# main.net
KiCad netlist of a schematic drawn in EAGLE
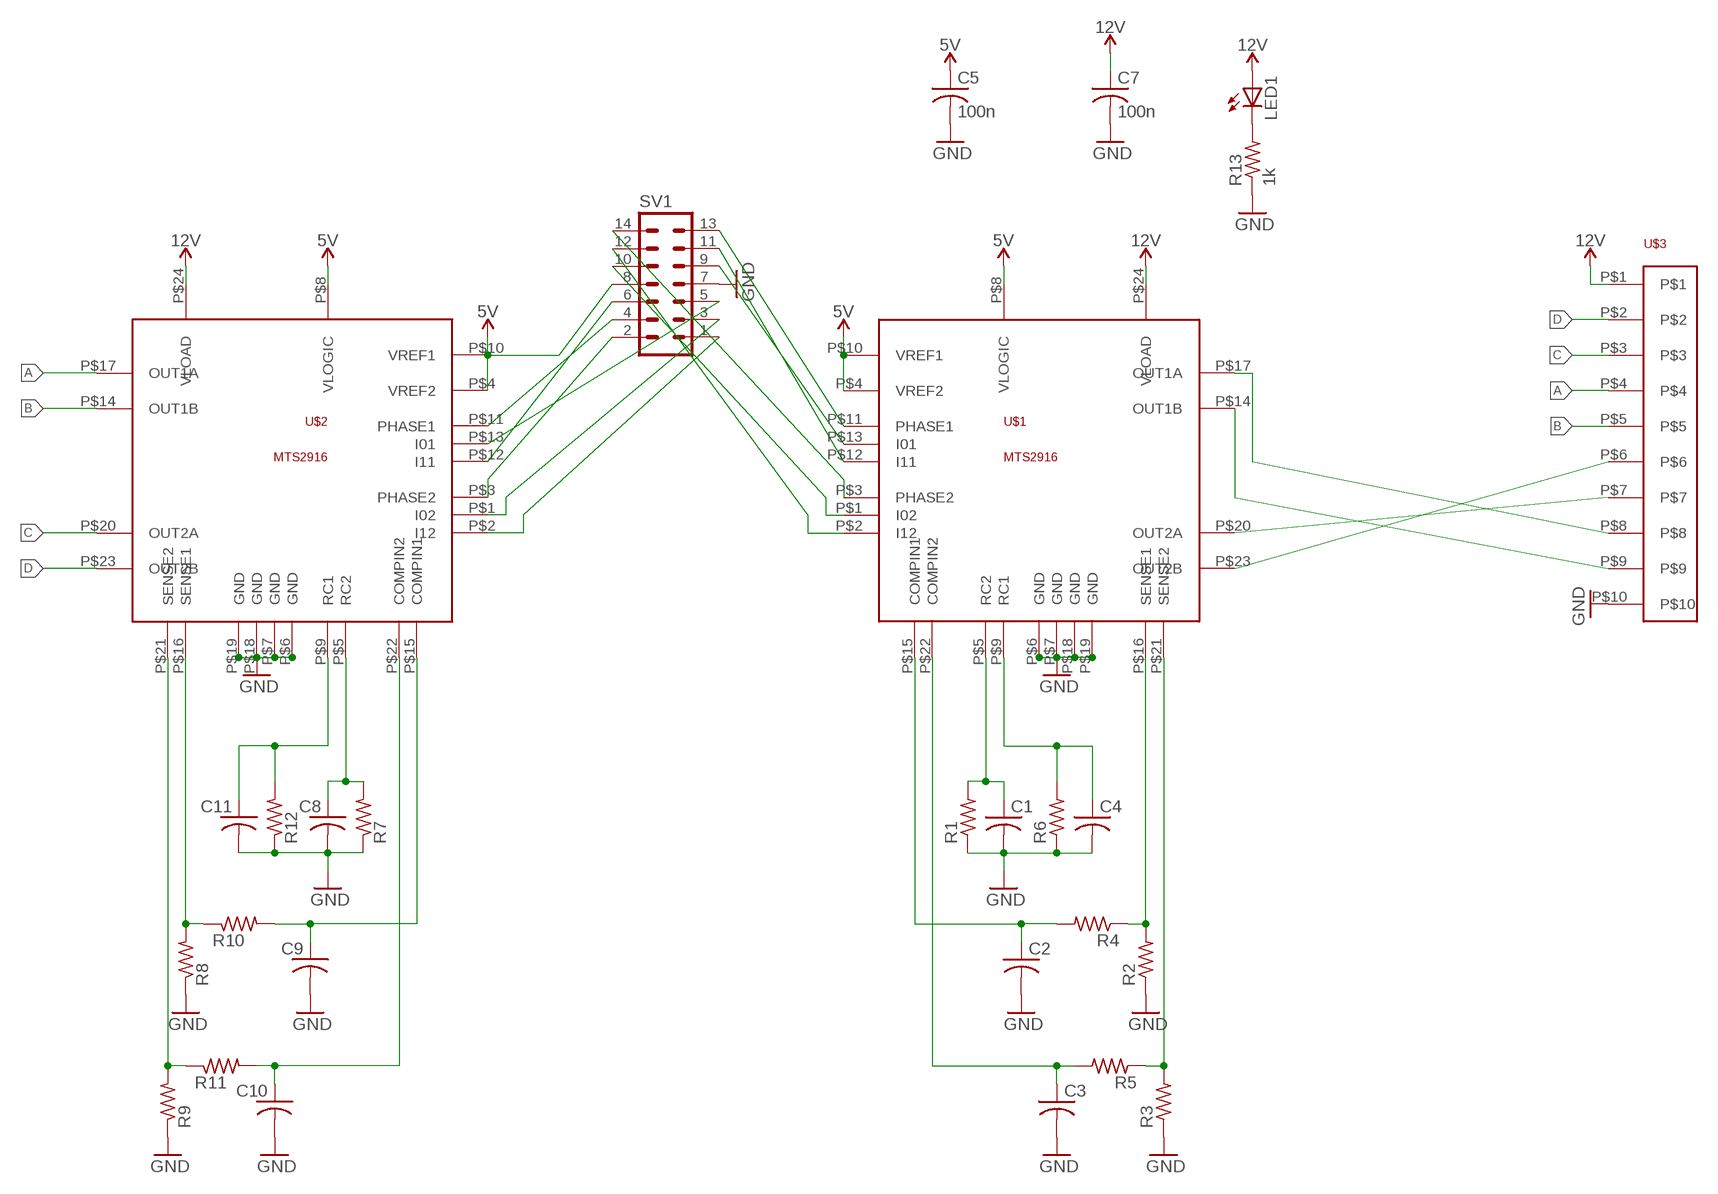
[diagram p0: schematic, sheet 1]

(export (version "E")
  (design (tool "Eeschema 10.0.6"))
  (components
    (comp (ref "C1")
      (value "C-US025-024X044")
      (footprint "eagle-import:C025-024X044")
      (libsource (lib "eagle-import") (part "C-US025-024X044"))
    )
    (comp (ref "C2")
      (value "C-US025-024X044")
      (footprint "eagle-import:C025-024X044")
      (libsource (lib "eagle-import") (part "C-US025-024X044"))
    )
    (comp (ref "C3")
      (value "C-US025-024X044")
      (footprint "eagle-import:C025-024X044")
      (libsource (lib "eagle-import") (part "C-US025-024X044"))
    )
    (comp (ref "C4")
      (value "C-US025-024X044")
      (footprint "eagle-import:C025-024X044")
      (libsource (lib "eagle-import") (part "C-US025-024X044"))
    )
    (comp (ref "C5")
      (value "100n")
      (footprint "eagle-import:C0603")
      (libsource (lib "eagle-import") (part "C-USC0603"))
    )
    (comp (ref "C7")
      (value "100n")
      (footprint "eagle-import:C0603")
      (libsource (lib "eagle-import") (part "C-USC0603"))
    )
    (comp (ref "C8")
      (value "C-US025-024X044")
      (footprint "eagle-import:C025-024X044")
      (libsource (lib "eagle-import") (part "C-US025-024X044"))
    )
    (comp (ref "C9")
      (value "C-US025-024X044")
      (footprint "eagle-import:C025-024X044")
      (libsource (lib "eagle-import") (part "C-US025-024X044"))
    )
    (comp (ref "C10")
      (value "C-US025-024X044")
      (footprint "eagle-import:C025-024X044")
      (libsource (lib "eagle-import") (part "C-US025-024X044"))
    )
    (comp (ref "C11")
      (value "C-US025-024X044")
      (footprint "eagle-import:C025-024X044")
      (libsource (lib "eagle-import") (part "C-US025-024X044"))
    )
    (comp (ref "LED1")
      (value "LED_ESML0603")
      (footprint "eagle-import:LED_SML0603")
      (libsource (lib "eagle-import") (part "LED_ESML0603"))
    )
    (comp (ref "R1")
      (value "R-US_M0805")
      (footprint "eagle-import:M0805")
      (libsource (lib "eagle-import") (part "R-US_M0805"))
    )
    (comp (ref "R2")
      (value "R-US_M0805")
      (footprint "eagle-import:M0805")
      (libsource (lib "eagle-import") (part "R-US_M0805"))
    )
    (comp (ref "R3")
      (value "R-US_M0805")
      (footprint "eagle-import:M0805")
      (libsource (lib "eagle-import") (part "R-US_M0805"))
    )
    (comp (ref "R4")
      (value "R-US_M0805")
      (footprint "eagle-import:M0805")
      (libsource (lib "eagle-import") (part "R-US_M0805"))
    )
    (comp (ref "R5")
      (value "R-US_M0805")
      (footprint "eagle-import:M0805")
      (libsource (lib "eagle-import") (part "R-US_M0805"))
    )
    (comp (ref "R6")
      (value "R-US_M0805")
      (footprint "eagle-import:M0805")
      (libsource (lib "eagle-import") (part "R-US_M0805"))
    )
    (comp (ref "R7")
      (value "R-US_M0805")
      (footprint "eagle-import:M0805")
      (libsource (lib "eagle-import") (part "R-US_M0805"))
    )
    (comp (ref "R8")
      (value "R-US_M0805")
      (footprint "eagle-import:M0805")
      (libsource (lib "eagle-import") (part "R-US_M0805"))
    )
    (comp (ref "R9")
      (value "R-US_M0805")
      (footprint "eagle-import:M0805")
      (libsource (lib "eagle-import") (part "R-US_M0805"))
    )
    (comp (ref "R10")
      (value "R-US_M0805")
      (footprint "eagle-import:M0805")
      (libsource (lib "eagle-import") (part "R-US_M0805"))
    )
    (comp (ref "R11")
      (value "R-US_M0805")
      (footprint "eagle-import:M0805")
      (libsource (lib "eagle-import") (part "R-US_M0805"))
    )
    (comp (ref "R12")
      (value "R-US_M0805")
      (footprint "eagle-import:M0805")
      (libsource (lib "eagle-import") (part "R-US_M0805"))
    )
    (comp (ref "R13")
      (value "1k")
      (footprint "eagle-import:R0603")
      (libsource (lib "eagle-import") (part "resistor_348_R-US_R0603"))
    )
    (comp (ref "SV1")
      (value "MA07-2")
      (footprint "eagle-import:MA07-2")
      (libsource (lib "eagle-import") (part "MA07-2"))
    )
    (comp (ref "U$1")
      (value "MTS2916")
      (footprint "eagle-import:SOP24")
      (libsource (lib "eagle-import") (part "MTS2916"))
    )
    (comp (ref "U$2")
      (value "MTS2916")
      (footprint "eagle-import:SOP24")
      (libsource (lib "eagle-import") (part "MTS2916"))
    )
    (comp (ref "U$3")
      (value "SCREWTERM_5MM_10WAY")
      (footprint "eagle-import:SCREWTERM_5MM_10WAY")
      (libsource (lib "eagle-import") (part "SCREWTERM_5MM_10WAY"))
    )
  )
  (nets
    (net (code "1") (name "5V") (class "Default")
      (node (ref "C5") (pin "1") (pinfunction "1_1") (pintype "passive"))
      (node (ref "SV1") (pin "8") (pinfunction "8_8") (pintype "passive"))
      (node (ref "U$1") (pin "P$10") (pinfunction "VREF1_P$10") (pintype "bidirectional"))
      (node (ref "U$1") (pin "P$4") (pinfunction "VREF2_P$4") (pintype "bidirectional"))
      (node (ref "U$1") (pin "P$8") (pinfunction "VLOGIC_P$8") (pintype "bidirectional"))
      (node (ref "U$2") (pin "P$10") (pinfunction "VREF1_P$10") (pintype "bidirectional"))
      (node (ref "U$2") (pin "P$4") (pinfunction "VREF2_P$4") (pintype "bidirectional"))
      (node (ref "U$2") (pin "P$8") (pinfunction "VLOGIC_P$8") (pintype "bidirectional"))
    )
    (net (code "2") (name "12V") (class "Default")
      (node (ref "C7") (pin "1") (pinfunction "1_1") (pintype "passive"))
      (node (ref "LED1") (pin "A") (pinfunction "A_A") (pintype "passive"))
      (node (ref "U$1") (pin "P$24") (pinfunction "VLOAD_P$24") (pintype "bidirectional"))
      (node (ref "U$2") (pin "P$24") (pinfunction "VLOAD_P$24") (pintype "bidirectional"))
      (node (ref "U$3") (pin "P$1") (pinfunction "P$1_P$1") (pintype "bidirectional"))
    )
    (net (code "3") (name "A") (class "Default")
      (node (ref "U$2") (pin "P$17") (pinfunction "OUT1A_P$17") (pintype "bidirectional"))
      (node (ref "U$3") (pin "P$4") (pinfunction "P$4_P$4") (pintype "bidirectional"))
    )
    (net (code "4") (name "B") (class "Default")
      (node (ref "U$2") (pin "P$14") (pinfunction "OUT1B_P$14") (pintype "bidirectional"))
      (node (ref "U$3") (pin "P$5") (pinfunction "P$5_P$5") (pintype "bidirectional"))
    )
    (net (code "5") (name "C") (class "Default")
      (node (ref "U$2") (pin "P$20") (pinfunction "OUT2A_P$20") (pintype "bidirectional"))
      (node (ref "U$3") (pin "P$3") (pinfunction "P$3_P$3") (pintype "bidirectional"))
    )
    (net (code "6") (name "D") (class "Default")
      (node (ref "U$2") (pin "P$23") (pinfunction "OUT2B_P$23") (pintype "bidirectional"))
      (node (ref "U$3") (pin "P$2") (pinfunction "P$2_P$2") (pintype "bidirectional"))
    )
    (net (code "7") (name "GND") (class "Default")
      (node (ref "C1") (pin "2") (pinfunction "2_2") (pintype "passive"))
      (node (ref "C10") (pin "2") (pinfunction "2_2") (pintype "passive"))
      (node (ref "C11") (pin "2") (pinfunction "2_2") (pintype "passive"))
      (node (ref "C2") (pin "2") (pinfunction "2_2") (pintype "passive"))
      (node (ref "C3") (pin "2") (pinfunction "2_2") (pintype "passive"))
      (node (ref "C4") (pin "2") (pinfunction "2_2") (pintype "passive"))
      (node (ref "C5") (pin "2") (pinfunction "2_2") (pintype "passive"))
      (node (ref "C7") (pin "2") (pinfunction "2_2") (pintype "passive"))
      (node (ref "C8") (pin "2") (pinfunction "2_2") (pintype "passive"))
      (node (ref "C9") (pin "2") (pinfunction "2_2") (pintype "passive"))
      (node (ref "R1") (pin "1") (pinfunction "1_1") (pintype "passive"))
      (node (ref "R12") (pin "1") (pinfunction "1_1") (pintype "passive"))
      (node (ref "R13") (pin "1") (pinfunction "1_1") (pintype "passive"))
      (node (ref "R2") (pin "1") (pinfunction "1_1") (pintype "passive"))
      (node (ref "R3") (pin "1") (pinfunction "1_1") (pintype "passive"))
      (node (ref "R6") (pin "1") (pinfunction "1_1") (pintype "passive"))
      (node (ref "R7") (pin "1") (pinfunction "1_1") (pintype "passive"))
      (node (ref "R8") (pin "1") (pinfunction "1_1") (pintype "passive"))
      (node (ref "R9") (pin "1") (pinfunction "1_1") (pintype "passive"))
      (node (ref "SV1") (pin "7") (pinfunction "7_7") (pintype "passive"))
      (node (ref "U$1") (pin "P$18") (pinfunction "GND_P$18") (pintype "bidirectional"))
      (node (ref "U$1") (pin "P$19") (pinfunction "GND_P$19") (pintype "bidirectional"))
      (node (ref "U$1") (pin "P$6") (pinfunction "GND_P$6") (pintype "bidirectional"))
      (node (ref "U$1") (pin "P$7") (pinfunction "GND_P$7") (pintype "bidirectional"))
      (node (ref "U$2") (pin "P$18") (pinfunction "GND_P$18") (pintype "bidirectional"))
      (node (ref "U$2") (pin "P$19") (pinfunction "GND_P$19") (pintype "bidirectional"))
      (node (ref "U$2") (pin "P$6") (pinfunction "GND_P$6") (pintype "bidirectional"))
      (node (ref "U$2") (pin "P$7") (pinfunction "GND_P$7") (pintype "bidirectional"))
      (node (ref "U$3") (pin "P$10") (pinfunction "P$10_P$10") (pintype "bidirectional"))
    )
    (net (code "8") (name "Net-(LED1-PadC)") (class "Default")
      (node (ref "LED1") (pin "C") (pinfunction "C_C") (pintype "passive"))
      (node (ref "R13") (pin "2") (pinfunction "2_2") (pintype "passive"))
    )
    (net (code "9") (name "Net-(U$1-COMPIN1)") (class "Default")
      (node (ref "C2") (pin "1") (pinfunction "1_1") (pintype "passive"))
      (node (ref "R4") (pin "2") (pinfunction "2_2") (pintype "passive"))
      (node (ref "U$1") (pin "P$15") (pinfunction "COMPIN1_P$15") (pintype "bidirectional"))
    )
    (net (code "10") (name "Net-(U$1-COMPIN2)") (class "Default")
      (node (ref "C3") (pin "1") (pinfunction "1_1") (pintype "passive"))
      (node (ref "R5") (pin "2") (pinfunction "2_2") (pintype "passive"))
      (node (ref "U$1") (pin "P$22") (pinfunction "COMPIN2_P$22") (pintype "bidirectional"))
    )
    (net (code "11") (name "Net-(U$1-I01)") (class "Default")
      (node (ref "SV1") (pin "9") (pinfunction "9_9") (pintype "passive"))
      (node (ref "U$1") (pin "P$13") (pinfunction "I01_P$13") (pintype "bidirectional"))
    )
    (net (code "12") (name "Net-(U$1-I02)") (class "Default")
      (node (ref "SV1") (pin "10") (pinfunction "10_10") (pintype "passive"))
      (node (ref "U$1") (pin "P$1") (pinfunction "I02_P$1") (pintype "bidirectional"))
    )
    (net (code "13") (name "Net-(U$1-I11)") (class "Default")
      (node (ref "SV1") (pin "11") (pinfunction "11_11") (pintype "passive"))
      (node (ref "U$1") (pin "P$12") (pinfunction "I11_P$12") (pintype "bidirectional"))
    )
    (net (code "14") (name "Net-(U$1-I12)") (class "Default")
      (node (ref "SV1") (pin "12") (pinfunction "12_12") (pintype "passive"))
      (node (ref "U$1") (pin "P$2") (pinfunction "I12_P$2") (pintype "bidirectional"))
    )
    (net (code "15") (name "Net-(U$1-OUT1A)") (class "Default")
      (node (ref "U$1") (pin "P$17") (pinfunction "OUT1A_P$17") (pintype "bidirectional"))
      (node (ref "U$3") (pin "P$8") (pinfunction "P$8_P$8") (pintype "bidirectional"))
    )
    (net (code "16") (name "Net-(U$1-OUT1B)") (class "Default")
      (node (ref "U$1") (pin "P$14") (pinfunction "OUT1B_P$14") (pintype "bidirectional"))
      (node (ref "U$3") (pin "P$9") (pinfunction "P$9_P$9") (pintype "bidirectional"))
    )
    (net (code "17") (name "Net-(U$1-OUT2A)") (class "Default")
      (node (ref "U$1") (pin "P$20") (pinfunction "OUT2A_P$20") (pintype "bidirectional"))
      (node (ref "U$3") (pin "P$7") (pinfunction "P$7_P$7") (pintype "bidirectional"))
    )
    (net (code "18") (name "Net-(U$1-OUT2B)") (class "Default")
      (node (ref "U$1") (pin "P$23") (pinfunction "OUT2B_P$23") (pintype "bidirectional"))
      (node (ref "U$3") (pin "P$6") (pinfunction "P$6_P$6") (pintype "bidirectional"))
    )
    (net (code "19") (name "Net-(U$1-PHASE1)") (class "Default")
      (node (ref "SV1") (pin "13") (pinfunction "13_13") (pintype "passive"))
      (node (ref "U$1") (pin "P$11") (pinfunction "PHASE1_P$11") (pintype "bidirectional"))
    )
    (net (code "20") (name "Net-(U$1-PHASE2)") (class "Default")
      (node (ref "SV1") (pin "14") (pinfunction "14_14") (pintype "passive"))
      (node (ref "U$1") (pin "P$3") (pinfunction "PHASE2_P$3") (pintype "bidirectional"))
    )
    (net (code "21") (name "Net-(U$1-RC1)") (class "Default")
      (node (ref "C4") (pin "1") (pinfunction "1_1") (pintype "passive"))
      (node (ref "R6") (pin "2") (pinfunction "2_2") (pintype "passive"))
      (node (ref "U$1") (pin "P$9") (pinfunction "RC1_P$9") (pintype "bidirectional"))
    )
    (net (code "22") (name "Net-(U$1-RC2)") (class "Default")
      (node (ref "C1") (pin "1") (pinfunction "1_1") (pintype "passive"))
      (node (ref "R1") (pin "2") (pinfunction "2_2") (pintype "passive"))
      (node (ref "U$1") (pin "P$5") (pinfunction "RC2_P$5") (pintype "bidirectional"))
    )
    (net (code "23") (name "Net-(U$1-SENSE1)") (class "Default")
      (node (ref "R2") (pin "2") (pinfunction "2_2") (pintype "passive"))
      (node (ref "R4") (pin "1") (pinfunction "1_1") (pintype "passive"))
      (node (ref "U$1") (pin "P$16") (pinfunction "SENSE1_P$16") (pintype "bidirectional"))
    )
    (net (code "24") (name "Net-(U$1-SENSE2)") (class "Default")
      (node (ref "R3") (pin "2") (pinfunction "2_2") (pintype "passive"))
      (node (ref "R5") (pin "1") (pinfunction "1_1") (pintype "passive"))
      (node (ref "U$1") (pin "P$21") (pinfunction "SENSE2_P$21") (pintype "bidirectional"))
    )
    (net (code "25") (name "Net-(U$2-COMPIN1)") (class "Default")
      (node (ref "C9") (pin "1") (pinfunction "1_1") (pintype "passive"))
      (node (ref "R10") (pin "2") (pinfunction "2_2") (pintype "passive"))
      (node (ref "U$2") (pin "P$15") (pinfunction "COMPIN1_P$15") (pintype "bidirectional"))
    )
    (net (code "26") (name "Net-(U$2-COMPIN2)") (class "Default")
      (node (ref "C10") (pin "1") (pinfunction "1_1") (pintype "passive"))
      (node (ref "R11") (pin "2") (pinfunction "2_2") (pintype "passive"))
      (node (ref "U$2") (pin "P$22") (pinfunction "COMPIN2_P$22") (pintype "bidirectional"))
    )
    (net (code "27") (name "Net-(U$2-I01)") (class "Default")
      (node (ref "SV1") (pin "5") (pinfunction "5_5") (pintype "passive"))
      (node (ref "U$2") (pin "P$13") (pinfunction "I01_P$13") (pintype "bidirectional"))
    )
    (net (code "28") (name "Net-(U$2-I02)") (class "Default")
      (node (ref "SV1") (pin "3") (pinfunction "3_3") (pintype "passive"))
      (node (ref "U$2") (pin "P$1") (pinfunction "I02_P$1") (pintype "bidirectional"))
    )
    (net (code "29") (name "Net-(U$2-I11)") (class "Default")
      (node (ref "SV1") (pin "6") (pinfunction "6_6") (pintype "passive"))
      (node (ref "U$2") (pin "P$12") (pinfunction "I11_P$12") (pintype "bidirectional"))
    )
    (net (code "30") (name "Net-(U$2-I12)") (class "Default")
      (node (ref "SV1") (pin "1") (pinfunction "1_1") (pintype "passive"))
      (node (ref "U$2") (pin "P$2") (pinfunction "I12_P$2") (pintype "bidirectional"))
    )
    (net (code "31") (name "Net-(U$2-PHASE1)") (class "Default")
      (node (ref "SV1") (pin "4") (pinfunction "4_4") (pintype "passive"))
      (node (ref "U$2") (pin "P$11") (pinfunction "PHASE1_P$11") (pintype "bidirectional"))
    )
    (net (code "32") (name "Net-(U$2-PHASE2)") (class "Default")
      (node (ref "SV1") (pin "2") (pinfunction "2_2") (pintype "passive"))
      (node (ref "U$2") (pin "P$3") (pinfunction "PHASE2_P$3") (pintype "bidirectional"))
    )
    (net (code "33") (name "Net-(U$2-RC1)") (class "Default")
      (node (ref "C11") (pin "1") (pinfunction "1_1") (pintype "passive"))
      (node (ref "R12") (pin "2") (pinfunction "2_2") (pintype "passive"))
      (node (ref "U$2") (pin "P$9") (pinfunction "RC1_P$9") (pintype "bidirectional"))
    )
    (net (code "34") (name "Net-(U$2-RC2)") (class "Default")
      (node (ref "C8") (pin "1") (pinfunction "1_1") (pintype "passive"))
      (node (ref "R7") (pin "2") (pinfunction "2_2") (pintype "passive"))
      (node (ref "U$2") (pin "P$5") (pinfunction "RC2_P$5") (pintype "bidirectional"))
    )
    (net (code "35") (name "Net-(U$2-SENSE1)") (class "Default")
      (node (ref "R10") (pin "1") (pinfunction "1_1") (pintype "passive"))
      (node (ref "R8") (pin "2") (pinfunction "2_2") (pintype "passive"))
      (node (ref "U$2") (pin "P$16") (pinfunction "SENSE1_P$16") (pintype "bidirectional"))
    )
    (net (code "36") (name "Net-(U$2-SENSE2)") (class "Default")
      (node (ref "R11") (pin "1") (pinfunction "1_1") (pintype "passive"))
      (node (ref "R9") (pin "2") (pinfunction "2_2") (pintype "passive"))
      (node (ref "U$2") (pin "P$21") (pinfunction "SENSE2_P$21") (pintype "bidirectional"))
    )
  )
)
